# W801.net
KiCad netlist of a schematic drawn in Altium Designer
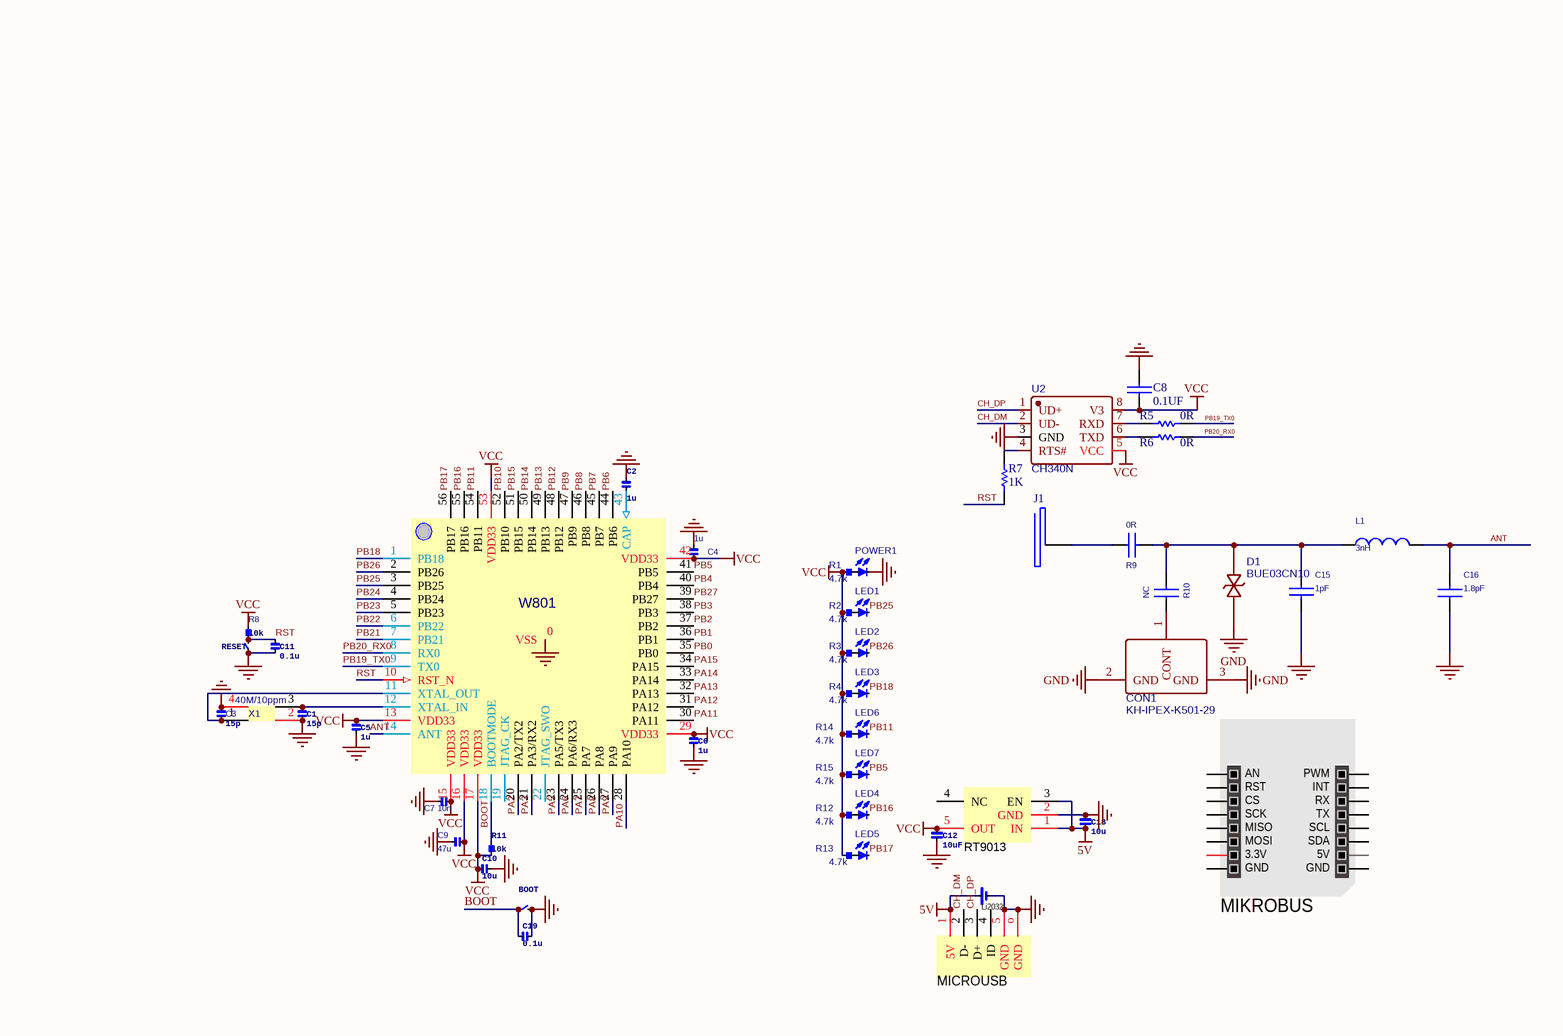
[diagram p0: W801.SchDoc]

(export (version "E")
  (design (tool "Eeschema 10.0.6"))
  (components
    (comp (ref "BOOT") (value "~") (libsource (lib "altium-import") (part "root_0_key_")))
    (comp (ref "C1") (value "15p") (footprint "0603") (libsource (lib "altium-import") (part "root_3_C_")))
    (comp (ref "C2") (value "1u") (footprint "0603") (libsource (lib "altium-import") (part "root_1_C_")))
    (comp (ref "C3") (value "15p") (footprint "0603") (libsource (lib "altium-import") (part "root_1_C_")))
    (comp (ref "C4") (value "1u") (footprint "0603") (libsource (lib "altium-import") (part "root_3_C_")))
    (comp (ref "C5") (value "1u") (footprint "0603") (libsource (lib "altium-import") (part "root_3_C_")))
    (comp (ref "C6") (value "1u") (footprint "0603") (libsource (lib "altium-import") (part "root_3_C_")))
    (comp (ref "C7") (value "10n") (footprint "0603") (libsource (lib "altium-import") (part "root_0_C_")))
    (comp (ref "C8")
      (value "0.1UF")
      (footprint "C 0603_L")
      (description "Capacitor")
      (libsource (lib "*") (part "CAP"))
    )
    (comp (ref "C9") (value "47u") (footprint "0805") (libsource (lib "altium-import") (part "root_2_C_")))
    (comp (ref "C10") (value "10u") (footprint "0603") (libsource (lib "altium-import") (part "root_0_C_")))
    (comp (ref "C11") (value "0.1u") (footprint "0603") (libsource (lib "altium-import") (part "root_3_C_")))
    (comp (ref "C12") (value "10uF") (footprint "1206") (libsource (lib "") (part "root_3_C__1")))
    (comp (ref "C15") (value "1pF") (footprint "C 0402_L") (libsource (lib "*") (part "CAP NP_Dup2")))
    (comp (ref "C16") (value "1.8pF") (footprint "C 0402_L") (libsource (lib "*") (part "CAP NP")))
    (comp (ref "C18") (value "10u") (footprint "1206") (libsource (lib "") (part "root_1_C__1")))
    (comp (ref "C19") (value "0.1u") (footprint "0603") (libsource (lib "altium-import") (part "root_0_C_")))
    (comp (ref "CON1")
      (value "KH-IPEX-K501-29")
      (footprint "SMA/UFLR/NI")
      (fields (field (name "BOM_SUPPLIER PART") "C411563") (field (name "CONTRIBUTOR") "LCSC"))
      (libsource (lib "altium-import") (part "root_0_KH-IPEX-K501-29_"))
    )
    (comp (ref "D1")
      (value "BUE03CN10")
      (footprint "X1-DFN1006-2_L1.0-W0.6-RD")
      (fields
        (field (name "BOM_SUPPLIER PART") "C492000")
        (field (name "BOM_MANUFACTURER PART") "PT05D5CE")
        (field (name "CONTRIBUTOR") "LCSC")
      )
      (libsource (lib "altium-import") (part "root_3_PT05D5CE_"))
    )
    (comp (ref "J1") (value "~") (footprint "TX1") (libsource (lib "Schlib1") (part "Component_1")))
    (comp (ref "L1") (value "3nH") (footprint "0402A") (libsource (lib "*") (part "INDUCTOR")))
    (comp (ref "LED1") (value "~") (footprint "0603") (libsource (lib "altium-import") (part "root_0_LED0_")))
    (comp (ref "LED2") (value "~") (footprint "0603") (libsource (lib "altium-import") (part "root_0_LED0_")))
    (comp (ref "LED3") (value "~") (footprint "0603") (libsource (lib "altium-import") (part "root_0_LED0_")))
    (comp (ref "LED4") (value "~") (footprint "0603") (libsource (lib "altium-import") (part "root_0_LED0_")))
    (comp (ref "LED5") (value "~") (footprint "0603") (libsource (lib "altium-import") (part "root_0_LED0_")))
    (comp (ref "LED6") (value "~") (footprint "0603") (libsource (lib "altium-import") (part "root_0_LED0_")))
    (comp (ref "LED7") (value "~") (footprint "0603") (libsource (lib "altium-import") (part "root_0_LED0_")))
    (comp (ref "Li2032") (value "~") (libsource (lib "altium-import") (part "root_0_Li2032_")))
    (comp (ref "MICROUSB")
      (value "~")
      (footprint "MICROUSB")
      (libsource (lib "altium-import") (part "root_1_MICROUSB_"))
    )
    (comp (ref "MIKROBUS")
      (value "~")
      (footprint "MIKROBUS")
      (libsource (lib "altium-import") (part "root_0_MIKROBUS_"))
    )
    (comp (ref "POWER1")
      (value "~")
      (footprint "0603")
      (libsource (lib "altium-import") (part "root_0_LED0_"))
    )
    (comp (ref "R1") (value "4.7k") (footprint "0603") (libsource (lib "altium-import") (part "root_2_R_")))
    (comp (ref "R2") (value "4.7k") (footprint "0603") (libsource (lib "altium-import") (part "root_2_R_")))
    (comp (ref "R3") (value "4.7k") (footprint "0603") (libsource (lib "altium-import") (part "root_2_R_")))
    (comp (ref "R4") (value "4.7k") (footprint "0603") (libsource (lib "altium-import") (part "root_2_R_")))
    (comp (ref "R5")
      (value "0R")
      (footprint "R 0603_L")
      (description "Resistor")
      (fields (field (name "PUBLISHER") "Altium Limited"))
      (libsource (lib "Miscellaneous Devices") (part "Res1"))
    )
    (comp (ref "R6")
      (value "0R")
      (footprint "R 0603_L")
      (description "Resistor")
      (fields (field (name "PUBLISHER") "Altium Limited"))
      (libsource (lib "Miscellaneous Devices") (part "Res1"))
    )
    (comp (ref "R7")
      (value "1K")
      (footprint "R 0603_L")
      (description "Resistor")
      (fields (field (name "PUBLISHER") "Altium Limited"))
      (libsource (lib "Miscellaneous Devices") (part "Res1"))
    )
    (comp (ref "R8") (value "10k") (footprint "0603") (libsource (lib "altium-import") (part "root_3_R_")))
    (comp (ref "R9") (value "0R") (footprint "R 0402_L") (libsource (lib "*") (part "CAP NP_Dup2")))
    (comp (ref "R10") (value "NC") (footprint "R 0402_L") (libsource (lib "*") (part "CAP NP_Dup2")))
    (comp (ref "R11") (value "10k") (footprint "0603") (libsource (lib "altium-import") (part "root_1_R_")))
    (comp (ref "R12") (value "4.7k") (footprint "0603") (libsource (lib "altium-import") (part "root_2_R_")))
    (comp (ref "R13") (value "4.7k") (footprint "0603") (libsource (lib "altium-import") (part "root_2_R_")))
    (comp (ref "R14") (value "4.7k") (footprint "0603") (libsource (lib "altium-import") (part "root_2_R_")))
    (comp (ref "R15") (value "4.7k") (footprint "0603") (libsource (lib "altium-import") (part "root_2_R_")))
    (comp (ref "RESET") (value "~") (libsource (lib "altium-import") (part "root_1_key_")))
    (comp (ref "RT9013")
      (value "~")
      (footprint "SGM2028")
      (libsource (lib "altium-import") (part "root_2_SGM2028_"))
    )
    (comp (ref "U2")
      (value "CH340N")
      (footprint "SOP8_L")
      (fields (field (name "BOM_SUPPLIER PART") "C506813") (field (name "CONTRIBUTOR") "LCSC"))
      (libsource (lib "Schlib1") (part "CH340N"))
    )
    (comp (ref "W801") (value "~") (footprint "W801") (libsource (lib "altium-import") (part "root_0_W801_")))
    (comp (ref "X1")
      (value "40M/10ppm")
      (footprint "3225")
      (libsource (lib "altium-import") (part "root_0_CRYSTAL_"))
    )
  )
  (nets
    (net (code "1") (name "/ANT") (class "Default")
      (node (ref "C16") (pin "2") (pinfunction "2_2") (pintype "passive"))
      (node (ref "L1") (pin "1") (pinfunction "1_1") (pintype "passive"))
      (node (ref "W801") (pin "14") (pinfunction "ANT_14") (pintype "passive"))
    )
    (net (code "2") (name "/BOOT") (class "Default")
      (node (ref "BOOT") (pin "1") (pinfunction "1_1") (pintype "passive"))
      (node (ref "C19") (pin "1") (pinfunction "1_1") (pintype "passive"))
      (node (ref "R11") (pin "2") (pinfunction "2_2") (pintype "passive"))
      (node (ref "W801") (pin "18") (pinfunction "BOOTMODE_18") (pintype "passive"))
    )
    (net (code "3") (name "/CH_DM") (class "Default")
      (node (ref "MICROUSB") (pin "2") (pinfunction "D-_2") (pintype "passive"))
      (node (ref "U2") (pin "2") (pinfunction "UD-_2") (pintype "passive"))
    )
    (net (code "4") (name "/CH_DP") (class "Default")
      (node (ref "MICROUSB") (pin "3") (pinfunction "D+_3") (pintype "passive"))
      (node (ref "U2") (pin "1") (pinfunction "UD+_1") (pintype "passive"))
    )
    (net (code "5") (name "/PA2") (class "Default")
      (node (ref "W801") (pin "20") (pinfunction "PA2/TX2_20") (pintype "passive"))
    )
    (net (code "6") (name "/PA3") (class "Default")
      (node (ref "W801") (pin "21") (pinfunction "PA3/RX2_21") (pintype "passive"))
    )
    (net (code "7") (name "/PA5") (class "Default")
      (node (ref "W801") (pin "23") (pinfunction "PA5/TX3_23") (pintype "passive"))
    )
    (net (code "8") (name "/PA6") (class "Default")
      (node (ref "W801") (pin "24") (pinfunction "PA6/RX3_24") (pintype "passive"))
    )
    (net (code "9") (name "/PA7") (class "Default")
      (node (ref "W801") (pin "25") (pinfunction "PA7_25") (pintype "passive"))
    )
    (net (code "10") (name "/PA8") (class "Default")
      (node (ref "W801") (pin "26") (pinfunction "PA8_26") (pintype "passive"))
    )
    (net (code "11") (name "/PA9") (class "Default")
      (node (ref "W801") (pin "27") (pinfunction "PA9_27") (pintype "passive"))
    )
    (net (code "12") (name "/PA10") (class "Default")
      (node (ref "W801") (pin "28") (pinfunction "PA10_28") (pintype "passive"))
    )
    (net (code "13") (name "/PA11") (class "Default")
      (node (ref "W801") (pin "30") (pinfunction "PA11_30") (pintype "passive"))
    )
    (net (code "14") (name "/PA12") (class "Default")
      (node (ref "W801") (pin "31") (pinfunction "PA12_31") (pintype "passive"))
    )
    (net (code "15") (name "/PA13") (class "Default")
      (node (ref "W801") (pin "32") (pinfunction "PA13_32") (pintype "passive"))
    )
    (net (code "16") (name "/PA14") (class "Default")
      (node (ref "W801") (pin "33") (pinfunction "PA14_33") (pintype "passive"))
    )
    (net (code "17") (name "/PA15") (class "Default")
      (node (ref "W801") (pin "34") (pinfunction "PA15_34") (pintype "passive"))
    )
    (net (code "18") (name "/PB0") (class "Default")
      (node (ref "W801") (pin "35") (pinfunction "PB0_35") (pintype "passive"))
    )
    (net (code "19") (name "/PB1") (class "Default")
      (node (ref "W801") (pin "36") (pinfunction "PB1_36") (pintype "passive"))
    )
    (net (code "20") (name "/PB2") (class "Default")
      (node (ref "W801") (pin "37") (pinfunction "PB2_37") (pintype "passive"))
    )
    (net (code "21") (name "/PB3") (class "Default")
      (node (ref "W801") (pin "38") (pinfunction "PB3_38") (pintype "passive"))
    )
    (net (code "22") (name "/PB4") (class "Default")
      (node (ref "W801") (pin "40") (pinfunction "PB4_40") (pintype "passive"))
    )
    (net (code "23") (name "/PB5") (class "Default")
      (node (ref "LED7") (pin "2") (pintype "passive"))
      (node (ref "W801") (pin "41") (pinfunction "PB5_41") (pintype "passive"))
    )
    (net (code "24") (name "/PB6") (class "Default")
      (node (ref "W801") (pin "44") (pinfunction "PB6_44") (pintype "passive"))
    )
    (net (code "25") (name "/PB7") (class "Default")
      (node (ref "W801") (pin "45") (pinfunction "PB7_45") (pintype "passive"))
    )
    (net (code "26") (name "/PB8") (class "Default")
      (node (ref "W801") (pin "46") (pinfunction "PB8_46") (pintype "passive"))
    )
    (net (code "27") (name "/PB9") (class "Default")
      (node (ref "W801") (pin "47") (pinfunction "PB9_47") (pintype "passive"))
    )
    (net (code "28") (name "/PB10") (class "Default")
      (node (ref "W801") (pin "52") (pinfunction "PB10_52") (pintype "passive"))
    )
    (net (code "29") (name "/PB11") (class "Default")
      (node (ref "LED6") (pin "2") (pintype "passive"))
      (node (ref "W801") (pin "54") (pinfunction "PB11_54") (pintype "passive"))
    )
    (net (code "30") (name "/PB12") (class "Default")
      (node (ref "W801") (pin "48") (pinfunction "PB12_48") (pintype "passive"))
    )
    (net (code "31") (name "/PB13") (class "Default")
      (node (ref "W801") (pin "49") (pinfunction "PB13_49") (pintype "passive"))
    )
    (net (code "32") (name "/PB14") (class "Default")
      (node (ref "W801") (pin "50") (pinfunction "PB14_50") (pintype "passive"))
    )
    (net (code "33") (name "/PB15") (class "Default")
      (node (ref "W801") (pin "51") (pinfunction "PB15_51") (pintype "passive"))
    )
    (net (code "34") (name "/PB16") (class "Default")
      (node (ref "LED4") (pin "2") (pintype "passive"))
      (node (ref "W801") (pin "55") (pinfunction "PB16_55") (pintype "passive"))
    )
    (net (code "35") (name "/PB17") (class "Default")
      (node (ref "LED5") (pin "2") (pintype "passive"))
      (node (ref "W801") (pin "56") (pinfunction "PB17_56") (pintype "passive"))
    )
    (net (code "36") (name "/PB18") (class "Default")
      (node (ref "LED3") (pin "2") (pintype "passive"))
      (node (ref "W801") (pin "1") (pinfunction "PB18_1") (pintype "passive"))
    )
    (net (code "37") (name "/PB19_TX0") (class "Default")
      (node (ref "R5") (pin "2") (pinfunction "2_2") (pintype "passive"))
      (node (ref "W801") (pin "9") (pinfunction "TX0_9") (pintype "passive"))
    )
    (net (code "38") (name "/PB20_RX0") (class "Default")
      (node (ref "R6") (pin "2") (pinfunction "2_2") (pintype "passive"))
      (node (ref "W801") (pin "8") (pinfunction "RX0_8") (pintype "passive"))
    )
    (net (code "39") (name "/PB21") (class "Default")
      (node (ref "W801") (pin "7") (pinfunction "PB21_7") (pintype "passive"))
    )
    (net (code "40") (name "/PB22") (class "Default")
      (node (ref "W801") (pin "6") (pinfunction "PB22_6") (pintype "passive"))
    )
    (net (code "41") (name "/PB23") (class "Default")
      (node (ref "W801") (pin "5") (pinfunction "PB23_5") (pintype "passive"))
    )
    (net (code "42") (name "/PB24") (class "Default")
      (node (ref "W801") (pin "4") (pinfunction "PB24_4") (pintype "passive"))
    )
    (net (code "43") (name "/PB25") (class "Default")
      (node (ref "LED1") (pin "2") (pintype "passive"))
      (node (ref "W801") (pin "3") (pinfunction "PB25_3") (pintype "passive"))
    )
    (net (code "44") (name "/PB26") (class "Default")
      (node (ref "LED2") (pin "2") (pintype "passive"))
      (node (ref "W801") (pin "2") (pinfunction "PB26_2") (pintype "passive"))
    )
    (net (code "45") (name "/PB27") (class "Default")
      (node (ref "W801") (pin "39") (pinfunction "PB27_39") (pintype "passive"))
    )
    (net (code "46") (name "/RST") (class "Default")
      (node (ref "C11") (pin "1") (pinfunction "1_1") (pintype "passive"))
      (node (ref "R7") (pin "1") (pinfunction "1_1") (pintype "passive"))
      (node (ref "R8") (pin "2") (pinfunction "2_2") (pintype "passive"))
      (node (ref "RESET") (pin "2") (pinfunction "2_2") (pintype "passive"))
      (node (ref "W801") (pin "10") (pinfunction "RST_N_10") (pintype "input"))
    )
    (net (code "47") (name "5V") (class "Default")
      (node (ref "C18") (pin "1") (pinfunction "1_1") (pintype "passive"))
      (node (ref "Li2032") (pin "1") (pinfunction "1_1") (pintype "passive"))
      (node (ref "MICROUSB") (pin "1") (pinfunction "5V_1") (pintype "passive"))
      (node (ref "RT9013") (pin "1") (pinfunction "IN_1") (pintype "passive"))
      (node (ref "RT9013") (pin "3") (pinfunction "EN_3") (pintype "passive"))
    )
    (net (code "48") (name "GND") (class "Default")
      (node (ref "BOOT") (pin "2") (pinfunction "2_2") (pintype "passive"))
      (node (ref "C1") (pin "2") (pinfunction "2_2") (pintype "passive"))
      (node (ref "C10") (pin "2") (pinfunction "2_2") (pintype "passive"))
      (node (ref "C11") (pin "2") (pinfunction "2_2") (pintype "passive"))
      (node (ref "C12") (pin "2") (pinfunction "2_2") (pintype "passive"))
      (node (ref "C15") (pin "2") (pinfunction "2_2") (pintype "passive"))
      (node (ref "C16") (pin "1") (pinfunction "1_1") (pintype "passive"))
      (node (ref "C18") (pin "2") (pinfunction "2_2") (pintype "passive"))
      (node (ref "C19") (pin "2") (pinfunction "2_2") (pintype "passive"))
      (node (ref "C2") (pin "2") (pinfunction "2_2") (pintype "passive"))
      (node (ref "C3") (pin "2") (pinfunction "2_2") (pintype "passive"))
      (node (ref "C4") (pin "1") (pinfunction "1_1") (pintype "passive"))
      (node (ref "C5") (pin "2") (pinfunction "2_2") (pintype "passive"))
      (node (ref "C6") (pin "2") (pinfunction "2_2") (pintype "passive"))
      (node (ref "C7") (pin "1") (pinfunction "1_1") (pintype "passive"))
      (node (ref "C8") (pin "1") (pinfunction "1_1") (pintype "passive"))
      (node (ref "C9") (pin "2") (pinfunction "2_2") (pintype "passive"))
      (node (ref "CON1") (pin "2") (pinfunction "GND_2") (pintype "passive"))
      (node (ref "CON1") (pin "3") (pinfunction "GND_3") (pintype "passive"))
      (node (ref "D1") (pin "2") (pinfunction "2_2") (pintype "passive"))
      (node (ref "Li2032") (pin "2") (pinfunction "2_2") (pintype "passive"))
      (node (ref "MICROUSB") (pin "5") (pinfunction "GND_5") (pintype "passive"))
      (node (ref "MICROUSB") (pin "o") (pinfunction "GND_o") (pintype "passive"))
      (node (ref "POWER1") (pin "2") (pintype "passive"))
      (node (ref "RESET") (pin "1") (pinfunction "1_1") (pintype "passive"))
      (node (ref "RT9013") (pin "2") (pinfunction "GND_2") (pintype "passive"))
      (node (ref "U2") (pin "3") (pinfunction "GND_3") (pintype "passive"))
      (node (ref "W801") (pin "0") (pinfunction "VSS_0") (pintype "passive"))
      (node (ref "X1") (pin "2") (pintype "passive"))
      (node (ref "X1") (pin "4") (pintype "passive"))
    )
    (net (code "49") (name "Net-(C15-Pad1)") (class "Default")
      (node (ref "C15") (pin "1") (pinfunction "1_1") (pintype "passive"))
      (node (ref "D1") (pin "1") (pinfunction "1_1") (pintype "passive"))
      (node (ref "L1") (pin "2") (pinfunction "2_2") (pintype "passive"))
      (node (ref "R10") (pin "2") (pinfunction "2_2") (pintype "passive"))
      (node (ref "R9") (pin "2") (pinfunction "2_2") (pintype "passive"))
    )
    (net (code "50") (name "Net-(CON1-CONT)") (class "Default")
      (node (ref "CON1") (pin "1") (pinfunction "CONT_1") (pintype "passive"))
      (node (ref "R10") (pin "1") (pinfunction "1_1") (pintype "passive"))
    )
    (net (code "51") (name "Net-(J1-Pad1)") (class "Default")
      (node (ref "J1") (pin "1") (pinfunction "1_1") (pintype "passive"))
      (node (ref "R9") (pin "1") (pinfunction "1_1") (pintype "passive"))
    )
    (net (code "52") (name "Net-(LED1-Pad1)") (class "Default")
      (node (ref "LED1") (pin "1") (pintype "passive"))
      (node (ref "R2") (pin "1") (pinfunction "1_1") (pintype "passive"))
    )
    (net (code "53") (name "Net-(LED2-Pad1)") (class "Default")
      (node (ref "LED2") (pin "1") (pintype "passive"))
      (node (ref "R3") (pin "1") (pinfunction "1_1") (pintype "passive"))
    )
    (net (code "54") (name "Net-(LED3-Pad1)") (class "Default")
      (node (ref "LED3") (pin "1") (pintype "passive"))
      (node (ref "R4") (pin "1") (pinfunction "1_1") (pintype "passive"))
    )
    (net (code "55") (name "Net-(LED4-Pad1)") (class "Default")
      (node (ref "LED4") (pin "1") (pintype "passive"))
      (node (ref "R12") (pin "1") (pinfunction "1_1") (pintype "passive"))
    )
    (net (code "56") (name "Net-(LED5-Pad1)") (class "Default")
      (node (ref "LED5") (pin "1") (pintype "passive"))
      (node (ref "R13") (pin "1") (pinfunction "1_1") (pintype "passive"))
    )
    (net (code "57") (name "Net-(LED6-Pad1)") (class "Default")
      (node (ref "LED6") (pin "1") (pintype "passive"))
      (node (ref "R14") (pin "1") (pinfunction "1_1") (pintype "passive"))
    )
    (net (code "58") (name "Net-(LED7-Pad1)") (class "Default")
      (node (ref "LED7") (pin "1") (pintype "passive"))
      (node (ref "R15") (pin "1") (pinfunction "1_1") (pintype "passive"))
    )
    (net (code "59") (name "Net-(POWER1-Pad1)") (class "Default")
      (node (ref "POWER1") (pin "1") (pintype "passive"))
      (node (ref "R1") (pin "1") (pinfunction "1_1") (pintype "passive"))
    )
    (net (code "60") (name "Net-(U2-RTS#)") (class "Default")
      (node (ref "R7") (pin "2") (pinfunction "2_2") (pintype "passive"))
      (node (ref "U2") (pin "4") (pinfunction "RTS#_4") (pintype "passive"))
    )
    (net (code "61") (name "Net-(U2-RXD)") (class "Default")
      (node (ref "R5") (pin "1") (pinfunction "1_1") (pintype "passive"))
      (node (ref "U2") (pin "7") (pinfunction "RXD_7") (pintype "passive"))
    )
    (net (code "62") (name "Net-(U2-TXD)") (class "Default")
      (node (ref "R6") (pin "1") (pinfunction "1_1") (pintype "passive"))
      (node (ref "U2") (pin "6") (pinfunction "TXD_6") (pintype "passive"))
    )
    (net (code "63") (name "Net-(W801-CAP)") (class "Default")
      (node (ref "C2") (pin "1") (pinfunction "1_1") (pintype "passive"))
      (node (ref "W801") (pin "43") (pinfunction "CAP_43") (pintype "input"))
    )
    (net (code "64") (name "Net-(W801-XTAL_IN)") (class "Default")
      (node (ref "C1") (pin "1") (pinfunction "1_1") (pintype "passive"))
      (node (ref "W801") (pin "12") (pinfunction "XTAL_IN_12") (pintype "passive"))
      (node (ref "X1") (pin "3") (pintype "passive"))
    )
    (net (code "65") (name "Net-(W801-XTAL_OUT)") (class "Default")
      (node (ref "C3") (pin "1") (pinfunction "1_1") (pintype "passive"))
      (node (ref "W801") (pin "11") (pinfunction "XTAL_OUT_11") (pintype "passive"))
      (node (ref "X1") (pin "1") (pintype "passive"))
    )
    (net (code "66") (name "VCC") (class "Default")
      (node (ref "C10") (pin "1") (pinfunction "1_1") (pintype "passive"))
      (node (ref "C12") (pin "1") (pinfunction "1_1") (pintype "passive"))
      (node (ref "C4") (pin "2") (pinfunction "2_2") (pintype "passive"))
      (node (ref "C5") (pin "1") (pinfunction "1_1") (pintype "passive"))
      (node (ref "C6") (pin "1") (pinfunction "1_1") (pintype "passive"))
      (node (ref "C7") (pin "2") (pinfunction "2_2") (pintype "passive"))
      (node (ref "C8") (pin "2") (pinfunction "2_2") (pintype "passive"))
      (node (ref "C9") (pin "1") (pinfunction "1_1") (pintype "passive"))
      (node (ref "R1") (pin "2") (pinfunction "2_2") (pintype "passive"))
      (node (ref "R11") (pin "1") (pinfunction "1_1") (pintype "passive"))
      (node (ref "R12") (pin "2") (pinfunction "2_2") (pintype "passive"))
      (node (ref "R13") (pin "2") (pinfunction "2_2") (pintype "passive"))
      (node (ref "R14") (pin "2") (pinfunction "2_2") (pintype "passive"))
      (node (ref "R15") (pin "2") (pinfunction "2_2") (pintype "passive"))
      (node (ref "R2") (pin "2") (pinfunction "2_2") (pintype "passive"))
      (node (ref "R3") (pin "2") (pinfunction "2_2") (pintype "passive"))
      (node (ref "R4") (pin "2") (pinfunction "2_2") (pintype "passive"))
      (node (ref "R8") (pin "1") (pinfunction "1_1") (pintype "passive"))
      (node (ref "RT9013") (pin "5") (pinfunction "OUT_5") (pintype "passive"))
      (node (ref "U2") (pin "5") (pinfunction "VCC_5") (pintype "passive"))
      (node (ref "U2") (pin "8") (pinfunction "V3_8") (pintype "passive"))
      (node (ref "W801") (pin "13") (pinfunction "VDD33_13") (pintype "passive"))
      (node (ref "W801") (pin "15") (pinfunction "VDD33_15") (pintype "passive"))
      (node (ref "W801") (pin "16") (pinfunction "VDD33_16") (pintype "passive"))
      (node (ref "W801") (pin "17") (pinfunction "VDD33_17") (pintype "passive"))
      (node (ref "W801") (pin "29") (pinfunction "VDD33_29") (pintype "passive"))
      (node (ref "W801") (pin "42") (pinfunction "VDD33_42") (pintype "passive"))
      (node (ref "W801") (pin "53") (pinfunction "VDD33_53") (pintype "passive"))
    )
    (net (code "67") (name "unconnected-(MICROUSB-ID-Pad4)") (class "Default")
      (node (ref "MICROUSB") (pin "4") (pinfunction "ID_4") (pintype "passive"))
    )
    (net (code "68") (name "unconnected-(MIKROBUS-3.3V-Pad7)") (class "Default")
      (node (ref "MIKROBUS") (pin "7") (pinfunction "3.3V_7") (pintype "passive"))
    )
    (net (code "69") (name "unconnected-(MIKROBUS-5V-Pad10)") (class "Default")
      (node (ref "MIKROBUS") (pin "10") (pinfunction "5V_10") (pintype "passive"))
    )
    (net (code "70") (name "unconnected-(MIKROBUS-AN-Pad1)") (class "Default")
      (node (ref "MIKROBUS") (pin "1") (pinfunction "AN_1") (pintype "passive"))
    )
    (net (code "71") (name "unconnected-(MIKROBUS-CS-Pad3)") (class "Default")
      (node (ref "MIKROBUS") (pin "3") (pinfunction "CS_3") (pintype "passive"))
    )
    (net (code "72") (name "unconnected-(MIKROBUS-GND-Pad8)") (class "Default")
      (node (ref "MIKROBUS") (pin "8") (pinfunction "GND_8") (pintype "passive"))
    )
    (net (code "73") (name "unconnected-(MIKROBUS-GND-Pad9)") (class "Default")
      (node (ref "MIKROBUS") (pin "9") (pinfunction "GND_9") (pintype "passive"))
    )
    (net (code "74") (name "unconnected-(MIKROBUS-INT-Pad15)") (class "Default")
      (node (ref "MIKROBUS") (pin "15") (pinfunction "INT_15") (pintype "passive"))
    )
    (net (code "75") (name "unconnected-(MIKROBUS-MISO-Pad5)") (class "Default")
      (node (ref "MIKROBUS") (pin "5") (pinfunction "MISO_5") (pintype "passive"))
    )
    (net (code "76") (name "unconnected-(MIKROBUS-MOSI-Pad6)") (class "Default")
      (node (ref "MIKROBUS") (pin "6") (pinfunction "MOSI_6") (pintype "passive"))
    )
    (net (code "77") (name "unconnected-(MIKROBUS-PWM-Pad16)") (class "Default")
      (node (ref "MIKROBUS") (pin "16") (pinfunction "PWM_16") (pintype "passive"))
    )
    (net (code "78") (name "unconnected-(MIKROBUS-RST-Pad2)") (class "Default")
      (node (ref "MIKROBUS") (pin "2") (pinfunction "RST_2") (pintype "passive"))
    )
    (net (code "79") (name "unconnected-(MIKROBUS-RX-Pad14)") (class "Default")
      (node (ref "MIKROBUS") (pin "14") (pinfunction "RX_14") (pintype "passive"))
    )
    (net (code "80") (name "unconnected-(MIKROBUS-SCK-Pad4)") (class "Default")
      (node (ref "MIKROBUS") (pin "4") (pinfunction "SCK_4") (pintype "passive"))
    )
    (net (code "81") (name "unconnected-(MIKROBUS-SCL-Pad12)") (class "Default")
      (node (ref "MIKROBUS") (pin "12") (pinfunction "SCL_12") (pintype "passive"))
    )
    (net (code "82") (name "unconnected-(MIKROBUS-SDA-Pad11)") (class "Default")
      (node (ref "MIKROBUS") (pin "11") (pinfunction "SDA_11") (pintype "passive"))
    )
    (net (code "83") (name "unconnected-(MIKROBUS-TX-Pad13)") (class "Default")
      (node (ref "MIKROBUS") (pin "13") (pinfunction "TX_13") (pintype "passive"))
    )
    (net (code "84") (name "unconnected-(RT9013-NC-Pad4)") (class "Default")
      (node (ref "RT9013") (pin "4") (pinfunction "NC_4") (pintype "passive"))
    )
    (net (code "85") (name "unconnected-(W801-JTAG_CK-Pad19)") (class "Default")
      (node (ref "W801") (pin "19") (pinfunction "JTAG_CK_19") (pintype "passive"))
    )
    (net (code "86") (name "unconnected-(W801-JTAG_SWO-Pad22)") (class "Default")
      (node (ref "W801") (pin "22") (pinfunction "JTAG_SWO_22") (pintype "passive"))
    )
  )
)
